# SINTETIZADOR_Y_MEZCLADOR.net
KiCad netlist of a schematic drawn in Altium Designer
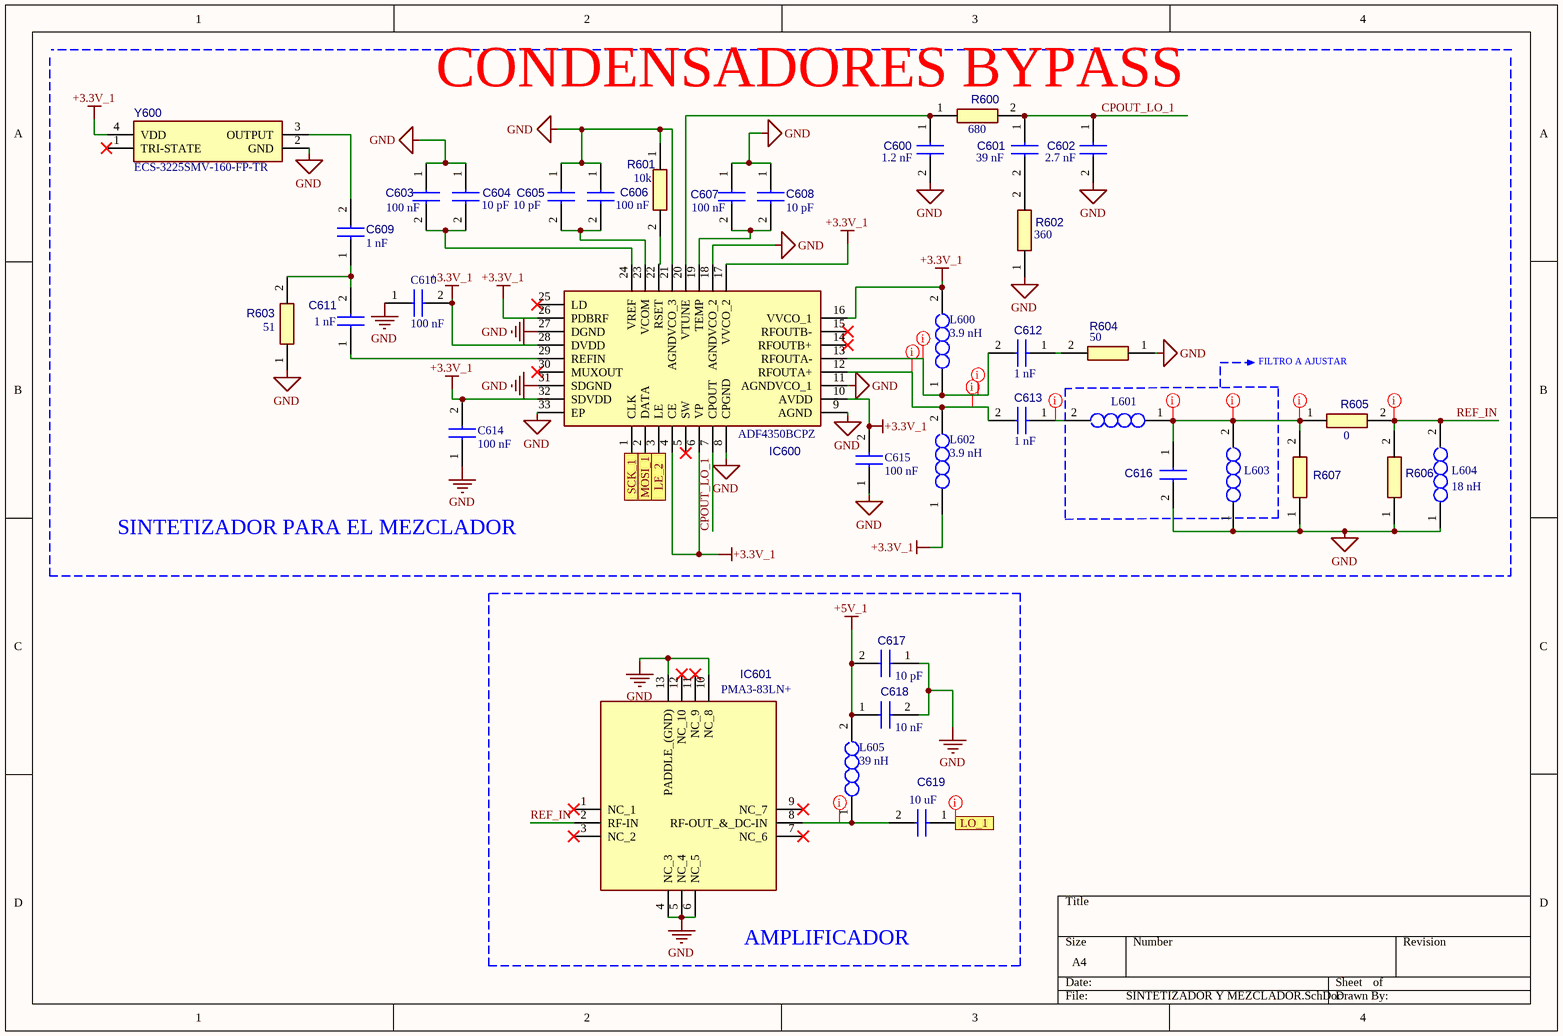
[diagram p0: SINTETIZADOR Y MEZCLADOR.SchDoc]

(export (version "E")
  (design (tool "Eeschema 10.0.6"))
  (components
    (comp (ref "C600")
      (value "1.2 nF")
      (footprint "SamacSys:C0603")
      (description "Capacitor")
      (fields (field (name "MANUFACTURER_PART_NUMBER") "C0603H470J5GACTU"))
      (libsource (lib "*") (part "C0603H470J5GACTU"))
    )
    (comp (ref "C601")
      (value "39 nF")
      (footprint "SamacSys:C0603")
      (description "Capacitor")
      (fields (field (name "MANUFACTURER_PART_NUMBER") "C0603H470J5GACTU"))
      (libsource (lib "*") (part "C0603H470J5GACTU"))
    )
    (comp (ref "C602")
      (value "2.7 nF")
      (footprint "SamacSys:C0603")
      (description "Capacitor")
      (fields (field (name "MANUFACTURER_PART_NUMBER") "C0603H470J5GACTU"))
      (libsource (lib "*") (part "C0603H470J5GACTU"))
    )
    (comp (ref "C603")
      (value "100 nF")
      (footprint "SamacSys:C0603")
      (description "Capacitor")
      (fields (field (name "MANUFACTURER_PART_NUMBER") "C0603H470J5GACTU"))
      (libsource (lib "*") (part "C0603H470J5GACTU"))
    )
    (comp (ref "C604")
      (value "10 pF")
      (footprint "SamacSys:C0603")
      (description "Capacitor")
      (fields (field (name "MANUFACTURER_PART_NUMBER") "C0603H470J5GACTU"))
      (libsource (lib "*") (part "C0603H470J5GACTU"))
    )
    (comp (ref "C605")
      (value "10 pF")
      (footprint "SamacSys:C0603")
      (description "Capacitor")
      (fields (field (name "MANUFACTURER_PART_NUMBER") "C0603H470J5GACTU"))
      (libsource (lib "*") (part "C0603H470J5GACTU"))
    )
    (comp (ref "C606")
      (value "100 nF")
      (footprint "SamacSys:C0603")
      (description "Capacitor")
      (fields (field (name "MANUFACTURER_PART_NUMBER") "C0603H470J5GACTU"))
      (libsource (lib "*") (part "C0603H470J5GACTU"))
    )
    (comp (ref "C607")
      (value "100 nF")
      (footprint "SamacSys:C0603")
      (description "Capacitor")
      (fields (field (name "MANUFACTURER_PART_NUMBER") "C0603H470J5GACTU"))
      (libsource (lib "*") (part "C0603H470J5GACTU"))
    )
    (comp (ref "C608")
      (value "10 pF")
      (footprint "SamacSys:C0603")
      (description "Capacitor")
      (fields (field (name "MANUFACTURER_PART_NUMBER") "C0603H470J5GACTU"))
      (libsource (lib "*") (part "C0603H470J5GACTU"))
    )
    (comp (ref "C609")
      (value "1 nF")
      (footprint "SamacSys:C0603")
      (description "Capacitor")
      (fields (field (name "MANUFACTURER_PART_NUMBER") "C0603H470J5GACTU"))
      (libsource (lib "*") (part "C0603H470J5GACTU"))
    )
    (comp (ref "C610")
      (value "100 nF")
      (footprint "SamacSys:C0603")
      (description "Capacitor")
      (fields (field (name "MANUFACTURER_PART_NUMBER") "C0603H470J5GACTU"))
      (libsource (lib "LIBRERIA_GEN_V2.0") (part "C0603H470J5GACTU"))
    )
    (comp (ref "C611")
      (value "1 nF")
      (footprint "SamacSys:C0603")
      (description "Capacitor")
      (fields (field (name "MANUFACTURER_PART_NUMBER") "C0603H470J5GACTU"))
      (libsource (lib "*") (part "C0603H470J5GACTU"))
    )
    (comp (ref "C612")
      (value "1 nF")
      (footprint "SamacSys:C0603")
      (description "Capacitor")
      (fields (field (name "MANUFACTURER_PART_NUMBER") "C0603H470J5GACTU"))
      (libsource (lib "*") (part "C0603H470J5GACTU"))
    )
    (comp (ref "C613")
      (value "1 nF")
      (footprint "SamacSys:C0603")
      (description "Capacitor")
      (fields (field (name "MANUFACTURER_PART_NUMBER") "C0603H470J5GACTU"))
      (libsource (lib "*") (part "C0603H470J5GACTU"))
    )
    (comp (ref "C614")
      (value "100 nF")
      (footprint "SamacSys:C0603")
      (description "Capacitor")
      (fields (field (name "MANUFACTURER_PART_NUMBER") "C0603H470J5GACTU"))
      (libsource (lib "LIBRERIA_GEN_V2.0") (part "C0603H470J5GACTU"))
    )
    (comp (ref "C615")
      (value "100 nF")
      (footprint "SamacSys:C0603")
      (description "Capacitor")
      (fields (field (name "MANUFACTURER_PART_NUMBER") "C0603H470J5GACTU"))
      (libsource (lib "LIBRERIA_GEN_V2.0") (part "C0603H470J5GACTU"))
    )
    (comp (ref "C616")
      (value "1.5 pF")
      (footprint "SamacSys:C0603")
      (description "Capacitor")
      (fields (field (name "MANUFACTURER_PART_NUMBER") "C0603H470J5GACTU"))
      (libsource (lib "*") (part "C0603H470J5GACTU"))
    )
    (comp (ref "C617")
      (value "10 pF")
      (footprint "SamacSys:C0603")
      (description "Capacitor")
      (fields (field (name "MANUFACTURER_PART_NUMBER") "C0603H470J5GACTU"))
      (libsource (lib "*") (part "C0603H470J5GACTU"))
    )
    (comp (ref "C618")
      (value "10 nF")
      (footprint "SamacSys:C0603")
      (description "Capacitor")
      (fields (field (name "MANUFACTURER_PART_NUMBER") "C0603H470J5GACTU"))
      (libsource (lib "*") (part "C0603H470J5GACTU"))
    )
    (comp (ref "C619")
      (value "10 uF")
      (footprint "SamacSys:C0603")
      (description "Capacitor")
      (fields (field (name "MANUFACTURER_PART_NUMBER") "C0603H470J5GACTU"))
      (libsource (lib "*") (part "C0603H470J5GACTU"))
    )
    (comp (ref "IC600")
      (value "ADF4350BCPZ")
      (footprint "SamacSys:QFN50P500X500X100-33N")
      (description "Integrated Circuit")
      (fields (field (name "MOUSER PART NUMBER") "584-ADF4350BCPZ"))
      (libsource (lib "*") (part "ADF4350BCPZ"))
    )
    (comp (ref "IC601")
      (value "PMA3-83LN+")
      (footprint "SamacSys:QFN51P300X300X89-13N")
      (description "Integrated Circuit")
      (fields (field (name "MOUSER PART NUMBER") "139-PMA3-83LN"))
      (libsource (lib "*") (part "PMA3-83LN+"))
    )
    (comp (ref "L600")
      (value "3.9 nH")
      (footprint "SamacSys:INDC1608X95N")
      (description "Inductor")
      (fields
        (field (name "MANUFACTURER_PART_NUMBER") "AIML-0603-100K-T")
        (field (name "MOUSER PART NUMBER") "815-AIML-0603-100KT")
      )
      (libsource (lib "*") (part "AIML-0603-100K-T"))
    )
    (comp (ref "L601")
      (value "3.9 nH")
      (footprint "SamacSys:INDC1608X95N")
      (description "Inductor")
      (fields
        (field (name "MANUFACTURER_PART_NUMBER") "AIML-0603-100K-T")
        (field (name "MOUSER PART NUMBER") "815-AIML-0603-100KT")
      )
      (libsource (lib "*") (part "AIML-0603-100K-T"))
    )
    (comp (ref "L602")
      (value "3.9 nH")
      (footprint "SamacSys:INDC1608X95N")
      (description "Inductor")
      (fields
        (field (name "MANUFACTURER_PART_NUMBER") "AIML-0603-100K-T")
        (field (name "MOUSER PART NUMBER") "815-AIML-0603-100KT")
      )
      (libsource (lib "*") (part "AIML-0603-100K-T"))
    )
    (comp (ref "L603")
      (value "1 nH")
      (footprint "SamacSys:INDC1608X95N")
      (description "Inductor")
      (fields
        (field (name "MANUFACTURER_PART_NUMBER") "AIML-0603-100K-T")
        (field (name "MOUSER PART NUMBER") "815-AIML-0603-100KT")
      )
      (libsource (lib "*") (part "AIML-0603-100K-T"))
    )
    (comp (ref "L604")
      (value "18 nH")
      (footprint "SamacSys:INDC1608X95N")
      (description "Inductor")
      (fields
        (field (name "MANUFACTURER_PART_NUMBER") "AIML-0603-100K-T")
        (field (name "MOUSER PART NUMBER") "815-AIML-0603-100KT")
      )
      (libsource (lib "*") (part "AIML-0603-100K-T"))
    )
    (comp (ref "L605")
      (value "39 nH")
      (footprint "SamacSys:INDC1608X95N")
      (description "Inductor")
      (fields
        (field (name "MANUFACTURER_PART_NUMBER") "AIML-0603-100K-T")
        (field (name "MOUSER PART NUMBER") "815-AIML-0603-100KT")
      )
      (libsource (lib "*") (part "AIML-0603-100K-T"))
    )
    (comp (ref "R600")
      (value "680")
      (footprint "SamacSys:RESC1608X55N")
      (description "Resistor")
      (fields
        (field (name "MANUFACTURER_PART_NUMBER") "CR0603-FX-1431ELF")
        (field (name "MOUSER PART NUMBER") "652-CR0603FX-1431ELF")
      )
      (libsource (lib "") (part "CR0603-FX-1431ELF_3"))
    )
    (comp (ref "R601")
      (value "10k")
      (footprint "SamacSys:RESC1608X55N")
      (description "Resistor")
      (fields
        (field (name "MANUFACTURER_PART_NUMBER") "CR0603-FX-1431ELF")
        (field (name "MOUSER PART NUMBER") "652-CR0603FX-1431ELF")
      )
      (libsource (lib "*") (part "CR0603-FX-1431ELF"))
    )
    (comp (ref "R602")
      (value "360")
      (footprint "SamacSys:RESC1608X55N")
      (description "Resistor")
      (fields
        (field (name "MANUFACTURER_PART_NUMBER") "CR0603-FX-1431ELF")
        (field (name "MOUSER PART NUMBER") "652-CR0603FX-1431ELF")
      )
      (libsource (lib "") (part "CR0603-FX-1431ELF_1"))
    )
    (comp (ref "R603")
      (value "51")
      (footprint "SamacSys:RESC1608X55N")
      (description "Resistor")
      (fields
        (field (name "MANUFACTURER_PART_NUMBER") "CR0603-FX-1431ELF")
        (field (name "MOUSER PART NUMBER") "652-CR0603FX-1431ELF")
      )
      (libsource (lib "") (part "CR0603-FX-1431ELF_1"))
    )
    (comp (ref "R604")
      (value "50")
      (footprint "SamacSys:RESC1608X55N")
      (description "Resistor")
      (fields
        (field (name "MANUFACTURER_PART_NUMBER") "CR0603-FX-1431ELF")
        (field (name "MOUSER PART NUMBER") "652-CR0603FX-1431ELF")
      )
      (libsource (lib "") (part "CR0603-FX-1431ELF_2"))
    )
    (comp (ref "R605")
      (value "0")
      (footprint "SamacSys:RESC1608X55N")
      (description "Resistor")
      (fields
        (field (name "MANUFACTURER_PART_NUMBER") "CR0603-FX-1431ELF")
        (field (name "MOUSER PART NUMBER") "652-CR0603FX-1431ELF")
      )
      (libsource (lib "") (part "CR0603-FX-1431ELF_3"))
    )
    (comp (ref "R606")
      (value "68")
      (footprint "SamacSys:RESC1608X55N")
      (description "Resistor")
      (fields
        (field (name "MANUFACTURER_PART_NUMBER") "CR0603-FX-1431ELF")
        (field (name "MOUSER PART NUMBER") "652-CR0603FX-1431ELF")
      )
      (libsource (lib "") (part "CR0603-FX-1431ELF_1"))
    )
    (comp (ref "R607")
      (value "68")
      (footprint "SamacSys:RESC1608X55N")
      (description "Resistor")
      (fields
        (field (name "MANUFACTURER_PART_NUMBER") "CR0603-FX-1431ELF")
        (field (name "MOUSER PART NUMBER") "652-CR0603FX-1431ELF")
      )
      (libsource (lib "") (part "CR0603-FX-1431ELF_1"))
    )
    (comp (ref "Y600")
      (value "ECS-3225SMV-160-FP-TR")
      (footprint "SamacSys:ECS3225SMV160FPTR")
      (description "Crystal or Oscillator")
      (fields (field (name "MOUSER PART NUMBER") "520-3225SMV-160-FPT"))
      (libsource (lib "*") (part "ECS-3225SMV-160-FP-TR"))
    )
  )
  (nets
    (net (code "1") (name "+3.3V_1") (class "Default")
      (node (ref "C610") (pin "2") (pinfunction "2_2") (pintype "passive"))
      (node (ref "C614") (pin "2") (pinfunction "2_2") (pintype "passive"))
      (node (ref "C615") (pin "2") (pinfunction "2_2") (pintype "passive"))
      (node (ref "IC600") (pin "10") (pinfunction "AVDD_10") (pintype "passive"))
      (node (ref "IC600") (pin "16") (pinfunction "VVCO_1_16") (pintype "passive"))
      (node (ref "IC600") (pin "17") (pinfunction "VVCO_2_17") (pintype "passive"))
      (node (ref "IC600") (pin "26") (pinfunction "PDBRF_26") (pintype "passive"))
      (node (ref "IC600") (pin "28") (pinfunction "DVDD_28") (pintype "passive"))
      (node (ref "IC600") (pin "32") (pinfunction "SDVDD_32") (pintype "passive"))
      (node (ref "IC600") (pin "4") (pinfunction "CE_4") (pintype "passive"))
      (node (ref "IC600") (pin "6") (pinfunction "VP_6") (pintype "passive"))
      (node (ref "L600") (pin "2") (pinfunction "2_2") (pintype "passive"))
      (node (ref "L602") (pin "1") (pinfunction "1_1") (pintype "passive"))
      (node (ref "Y600") (pin "4") (pinfunction "VDD_4") (pintype "passive"))
    )
    (net (code "2") (name "+5V_1") (class "Default")
      (node (ref "C617") (pin "2") (pinfunction "2_2") (pintype "passive"))
      (node (ref "C618") (pin "1") (pinfunction "1_1") (pintype "passive"))
      (node (ref "L605") (pin "2") (pinfunction "2_2") (pintype "passive"))
    )
    (net (code "3") (name "/CPOUT_LO_1") (class "Default")
      (node (ref "C601") (pin "1") (pinfunction "1_1") (pintype "passive"))
      (node (ref "C602") (pin "1") (pinfunction "1_1") (pintype "passive"))
      (node (ref "IC600") (pin "7") (pinfunction "CPOUT_7") (pintype "passive"))
      (node (ref "R600") (pin "2") (pinfunction "2_2") (pintype "passive"))
    )
    (net (code "4") (name "/LE_2") (class "Default")
      (node (ref "IC600") (pin "3") (pinfunction "LE_3") (pintype "passive"))
    )
    (net (code "5") (name "/LO_1") (class "Default")
      (node (ref "C619") (pin "1") (pinfunction "1_1") (pintype "passive"))
    )
    (net (code "6") (name "/MOSI_1") (class "Default")
      (node (ref "IC600") (pin "2") (pinfunction "DATA_2") (pintype "passive"))
    )
    (net (code "7") (name "/REF_IN") (class "Default")
      (node (ref "IC601") (pin "2") (pinfunction "RF-IN_2") (pintype "passive"))
      (node (ref "L604") (pin "2") (pinfunction "2_2") (pintype "passive"))
      (node (ref "R605") (pin "2") (pinfunction "2_2") (pintype "passive"))
      (node (ref "R606") (pin "2") (pinfunction "2_2") (pintype "passive"))
    )
    (net (code "8") (name "/SCK_1") (class "Default")
      (node (ref "IC600") (pin "1") (pinfunction "CLK_1") (pintype "passive"))
    )
    (net (code "9") (name "GND") (class "Default")
      (node (ref "C600") (pin "2") (pinfunction "2_2") (pintype "passive"))
      (node (ref "C602") (pin "2") (pinfunction "2_2") (pintype "passive"))
      (node (ref "C603") (pin "1") (pinfunction "1_1") (pintype "passive"))
      (node (ref "C604") (pin "1") (pinfunction "1_1") (pintype "passive"))
      (node (ref "C605") (pin "1") (pinfunction "1_1") (pintype "passive"))
      (node (ref "C606") (pin "1") (pinfunction "1_1") (pintype "passive"))
      (node (ref "C607") (pin "1") (pinfunction "1_1") (pintype "passive"))
      (node (ref "C608") (pin "1") (pinfunction "1_1") (pintype "passive"))
      (node (ref "C610") (pin "1") (pinfunction "1_1") (pintype "passive"))
      (node (ref "C614") (pin "1") (pinfunction "1_1") (pintype "passive"))
      (node (ref "C615") (pin "1") (pinfunction "1_1") (pintype "passive"))
      (node (ref "C616") (pin "2") (pinfunction "2_2") (pintype "passive"))
      (node (ref "C617") (pin "1") (pinfunction "1_1") (pintype "passive"))
      (node (ref "C618") (pin "2") (pinfunction "2_2") (pintype "passive"))
      (node (ref "IC600") (pin "11") (pinfunction "AGNDVCO_1_11") (pintype "passive"))
      (node (ref "IC600") (pin "18") (pinfunction "AGNDVCO_2_18") (pintype "passive"))
      (node (ref "IC600") (pin "21") (pinfunction "AGNDVCO_3_21") (pintype "passive"))
      (node (ref "IC600") (pin "27") (pinfunction "DGND_27") (pintype "passive"))
      (node (ref "IC600") (pin "31") (pinfunction "SDGND_31") (pintype "passive"))
      (node (ref "IC600") (pin "33") (pinfunction "EP_33") (pintype "passive"))
      (node (ref "IC600") (pin "8") (pinfunction "CPGND_8") (pintype "passive"))
      (node (ref "IC600") (pin "9") (pinfunction "AGND_9") (pintype "passive"))
      (node (ref "IC601") (pin "10") (pinfunction "NC_8_10") (pintype "passive"))
      (node (ref "IC601") (pin "13") (pinfunction "PADDLE_(GND)_13") (pintype "passive"))
      (node (ref "IC601") (pin "4") (pinfunction "NC_3_4") (pintype "passive"))
      (node (ref "IC601") (pin "5") (pinfunction "NC_4_5") (pintype "passive"))
      (node (ref "IC601") (pin "6") (pinfunction "NC_5_6") (pintype "passive"))
      (node (ref "L603") (pin "1") (pinfunction "1_1") (pintype "passive"))
      (node (ref "L604") (pin "1") (pinfunction "1_1") (pintype "passive"))
      (node (ref "R601") (pin "1") (pinfunction "1_1") (pintype "passive"))
      (node (ref "R602") (pin "1") (pinfunction "1_1") (pintype "passive"))
      (node (ref "R603") (pin "1") (pinfunction "1_1") (pintype "passive"))
      (node (ref "R604") (pin "1") (pinfunction "1_1") (pintype "passive"))
      (node (ref "R606") (pin "1") (pinfunction "1_1") (pintype "passive"))
      (node (ref "R607") (pin "1") (pinfunction "1_1") (pintype "passive"))
      (node (ref "Y600") (pin "2") (pinfunction "GND_2") (pintype "passive"))
    )
    (net (code "10") (name "Net-(C601-Pad2)") (class "Default")
      (node (ref "C601") (pin "2") (pinfunction "2_2") (pintype "passive"))
      (node (ref "R602") (pin "2") (pinfunction "2_2") (pintype "passive"))
    )
    (net (code "11") (name "Net-(C609-Pad1)") (class "Default")
      (node (ref "C609") (pin "1") (pinfunction "1_1") (pintype "passive"))
      (node (ref "C611") (pin "2") (pinfunction "2_2") (pintype "passive"))
      (node (ref "R603") (pin "2") (pinfunction "2_2") (pintype "passive"))
    )
    (net (code "12") (name "Net-(C612-Pad1)") (class "Default")
      (node (ref "C612") (pin "1") (pinfunction "1_1") (pintype "passive"))
      (node (ref "R604") (pin "2") (pinfunction "2_2") (pintype "passive"))
    )
    (net (code "13") (name "Net-(C613-Pad1)") (class "Default")
      (node (ref "C613") (pin "1") (pinfunction "1_1") (pintype "passive"))
      (node (ref "L601") (pin "2") (pinfunction "2_2") (pintype "passive"))
    )
    (net (code "14") (name "Net-(C616-Pad1)") (class "Default")
      (node (ref "C616") (pin "1") (pinfunction "1_1") (pintype "passive"))
      (node (ref "L601") (pin "1") (pinfunction "1_1") (pintype "passive"))
      (node (ref "L603") (pin "2") (pinfunction "2_2") (pintype "passive"))
      (node (ref "R605") (pin "1") (pinfunction "1_1") (pintype "passive"))
      (node (ref "R607") (pin "2") (pinfunction "2_2") (pintype "passive"))
    )
    (net (code "15") (name "Net-(IC600-REFIN)") (class "Default")
      (node (ref "C611") (pin "1") (pinfunction "1_1") (pintype "passive"))
      (node (ref "IC600") (pin "29") (pinfunction "REFIN_29") (pintype "passive"))
    )
    (net (code "16") (name "Net-(IC600-RFOUTA+)") (class "Default")
      (node (ref "C613") (pin "2") (pinfunction "2_2") (pintype "passive"))
      (node (ref "IC600") (pin "12") (pinfunction "RFOUTA+_12") (pintype "passive"))
      (node (ref "L602") (pin "2") (pinfunction "2_2") (pintype "passive"))
    )
    (net (code "17") (name "Net-(IC600-RFOUTA-)") (class "Default")
      (node (ref "C612") (pin "2") (pinfunction "2_2") (pintype "passive"))
      (node (ref "IC600") (pin "13") (pinfunction "RFOUTA-_13") (pintype "passive"))
      (node (ref "L600") (pin "1") (pinfunction "1_1") (pintype "passive"))
    )
    (net (code "18") (name "Net-(IC600-RSET)") (class "Default")
      (node (ref "IC600") (pin "22") (pinfunction "RSET_22") (pintype "passive"))
      (node (ref "R601") (pin "2") (pinfunction "2_2") (pintype "passive"))
    )
    (net (code "19") (name "Net-(IC600-TEMP)") (class "Default")
      (node (ref "C607") (pin "2") (pinfunction "2_2") (pintype "passive"))
      (node (ref "C608") (pin "2") (pinfunction "2_2") (pintype "passive"))
      (node (ref "IC600") (pin "19") (pinfunction "TEMP_19") (pintype "passive"))
    )
    (net (code "20") (name "Net-(IC600-VCOM)") (class "Default")
      (node (ref "C605") (pin "2") (pinfunction "2_2") (pintype "passive"))
      (node (ref "C606") (pin "2") (pinfunction "2_2") (pintype "passive"))
      (node (ref "IC600") (pin "23") (pinfunction "VCOM_23") (pintype "passive"))
    )
    (net (code "21") (name "Net-(IC600-VREF)") (class "Default")
      (node (ref "C603") (pin "2") (pinfunction "2_2") (pintype "passive"))
      (node (ref "C604") (pin "2") (pinfunction "2_2") (pintype "passive"))
      (node (ref "IC600") (pin "24") (pinfunction "VREF_24") (pintype "passive"))
    )
    (net (code "22") (name "Net-(IC600-VTUNE)") (class "Default")
      (node (ref "C600") (pin "1") (pinfunction "1_1") (pintype "passive"))
      (node (ref "IC600") (pin "20") (pinfunction "VTUNE_20") (pintype "passive"))
      (node (ref "R600") (pin "1") (pinfunction "1_1") (pintype "passive"))
    )
    (net (code "23") (name "Net-(IC601-RF-OUT_&_DC-IN)") (class "Default")
      (node (ref "C619") (pin "2") (pinfunction "2_2") (pintype "passive"))
      (node (ref "IC601") (pin "8") (pinfunction "RF-OUT_&_DC-IN_8") (pintype "passive"))
      (node (ref "L605") (pin "1") (pinfunction "1_1") (pintype "passive"))
    )
    (net (code "24") (name "Net-(Y600-OUTPUT)") (class "Default")
      (node (ref "C609") (pin "2") (pinfunction "2_2") (pintype "passive"))
      (node (ref "Y600") (pin "3") (pinfunction "OUTPUT_3") (pintype "passive"))
    )
    (net (code "25") (name "unconnected-(IC600-LD-Pad25)") (class "Default")
      (node (ref "IC600") (pin "25") (pinfunction "LD_25") (pintype "passive+no_connect"))
    )
    (net (code "26") (name "unconnected-(IC600-MUXOUT-Pad30)") (class "Default")
      (node (ref "IC600") (pin "30") (pinfunction "MUXOUT_30") (pintype "passive+no_connect"))
    )
    (net (code "27") (name "unconnected-(IC600-RFOUTB+-Pad14)") (class "Default")
      (node (ref "IC600") (pin "14") (pinfunction "RFOUTB+_14") (pintype "passive+no_connect"))
    )
    (net (code "28") (name "unconnected-(IC600-RFOUTB--Pad15)") (class "Default")
      (node (ref "IC600") (pin "15") (pinfunction "RFOUTB-_15") (pintype "passive+no_connect"))
    )
    (net (code "29") (name "unconnected-(IC600-SW-Pad5)") (class "Default")
      (node (ref "IC600") (pin "5") (pinfunction "SW_5") (pintype "passive+no_connect"))
    )
    (net (code "30") (name "unconnected-(IC601-NC_1-Pad1)") (class "Default")
      (node (ref "IC601") (pin "1") (pinfunction "NC_1_1") (pintype "passive+no_connect"))
    )
    (net (code "31") (name "unconnected-(IC601-NC_2-Pad3)") (class "Default")
      (node (ref "IC601") (pin "3") (pinfunction "NC_2_3") (pintype "passive+no_connect"))
    )
    (net (code "32") (name "unconnected-(IC601-NC_6-Pad7)") (class "Default")
      (node (ref "IC601") (pin "7") (pinfunction "NC_6_7") (pintype "passive+no_connect"))
    )
    (net (code "33") (name "unconnected-(IC601-NC_7-Pad9)") (class "Default")
      (node (ref "IC601") (pin "9") (pinfunction "NC_7_9") (pintype "passive+no_connect"))
    )
    (net (code "34") (name "unconnected-(IC601-NC_9-Pad11)") (class "Default")
      (node (ref "IC601") (pin "11") (pinfunction "NC_9_11") (pintype "passive+no_connect"))
    )
    (net (code "35") (name "unconnected-(IC601-NC_10-Pad12)") (class "Default")
      (node (ref "IC601") (pin "12") (pinfunction "NC_10_12") (pintype "passive+no_connect"))
    )
    (net (code "36") (name "unconnected-(Y600-TRI-STATE-Pad1)") (class "Default")
      (node (ref "Y600") (pin "1") (pinfunction "TRI-STATE_1") (pintype "passive+no_connect"))
    )
  )
)
